# A-GSM.net
KiCad netlist of a schematic drawn in Altium Designer
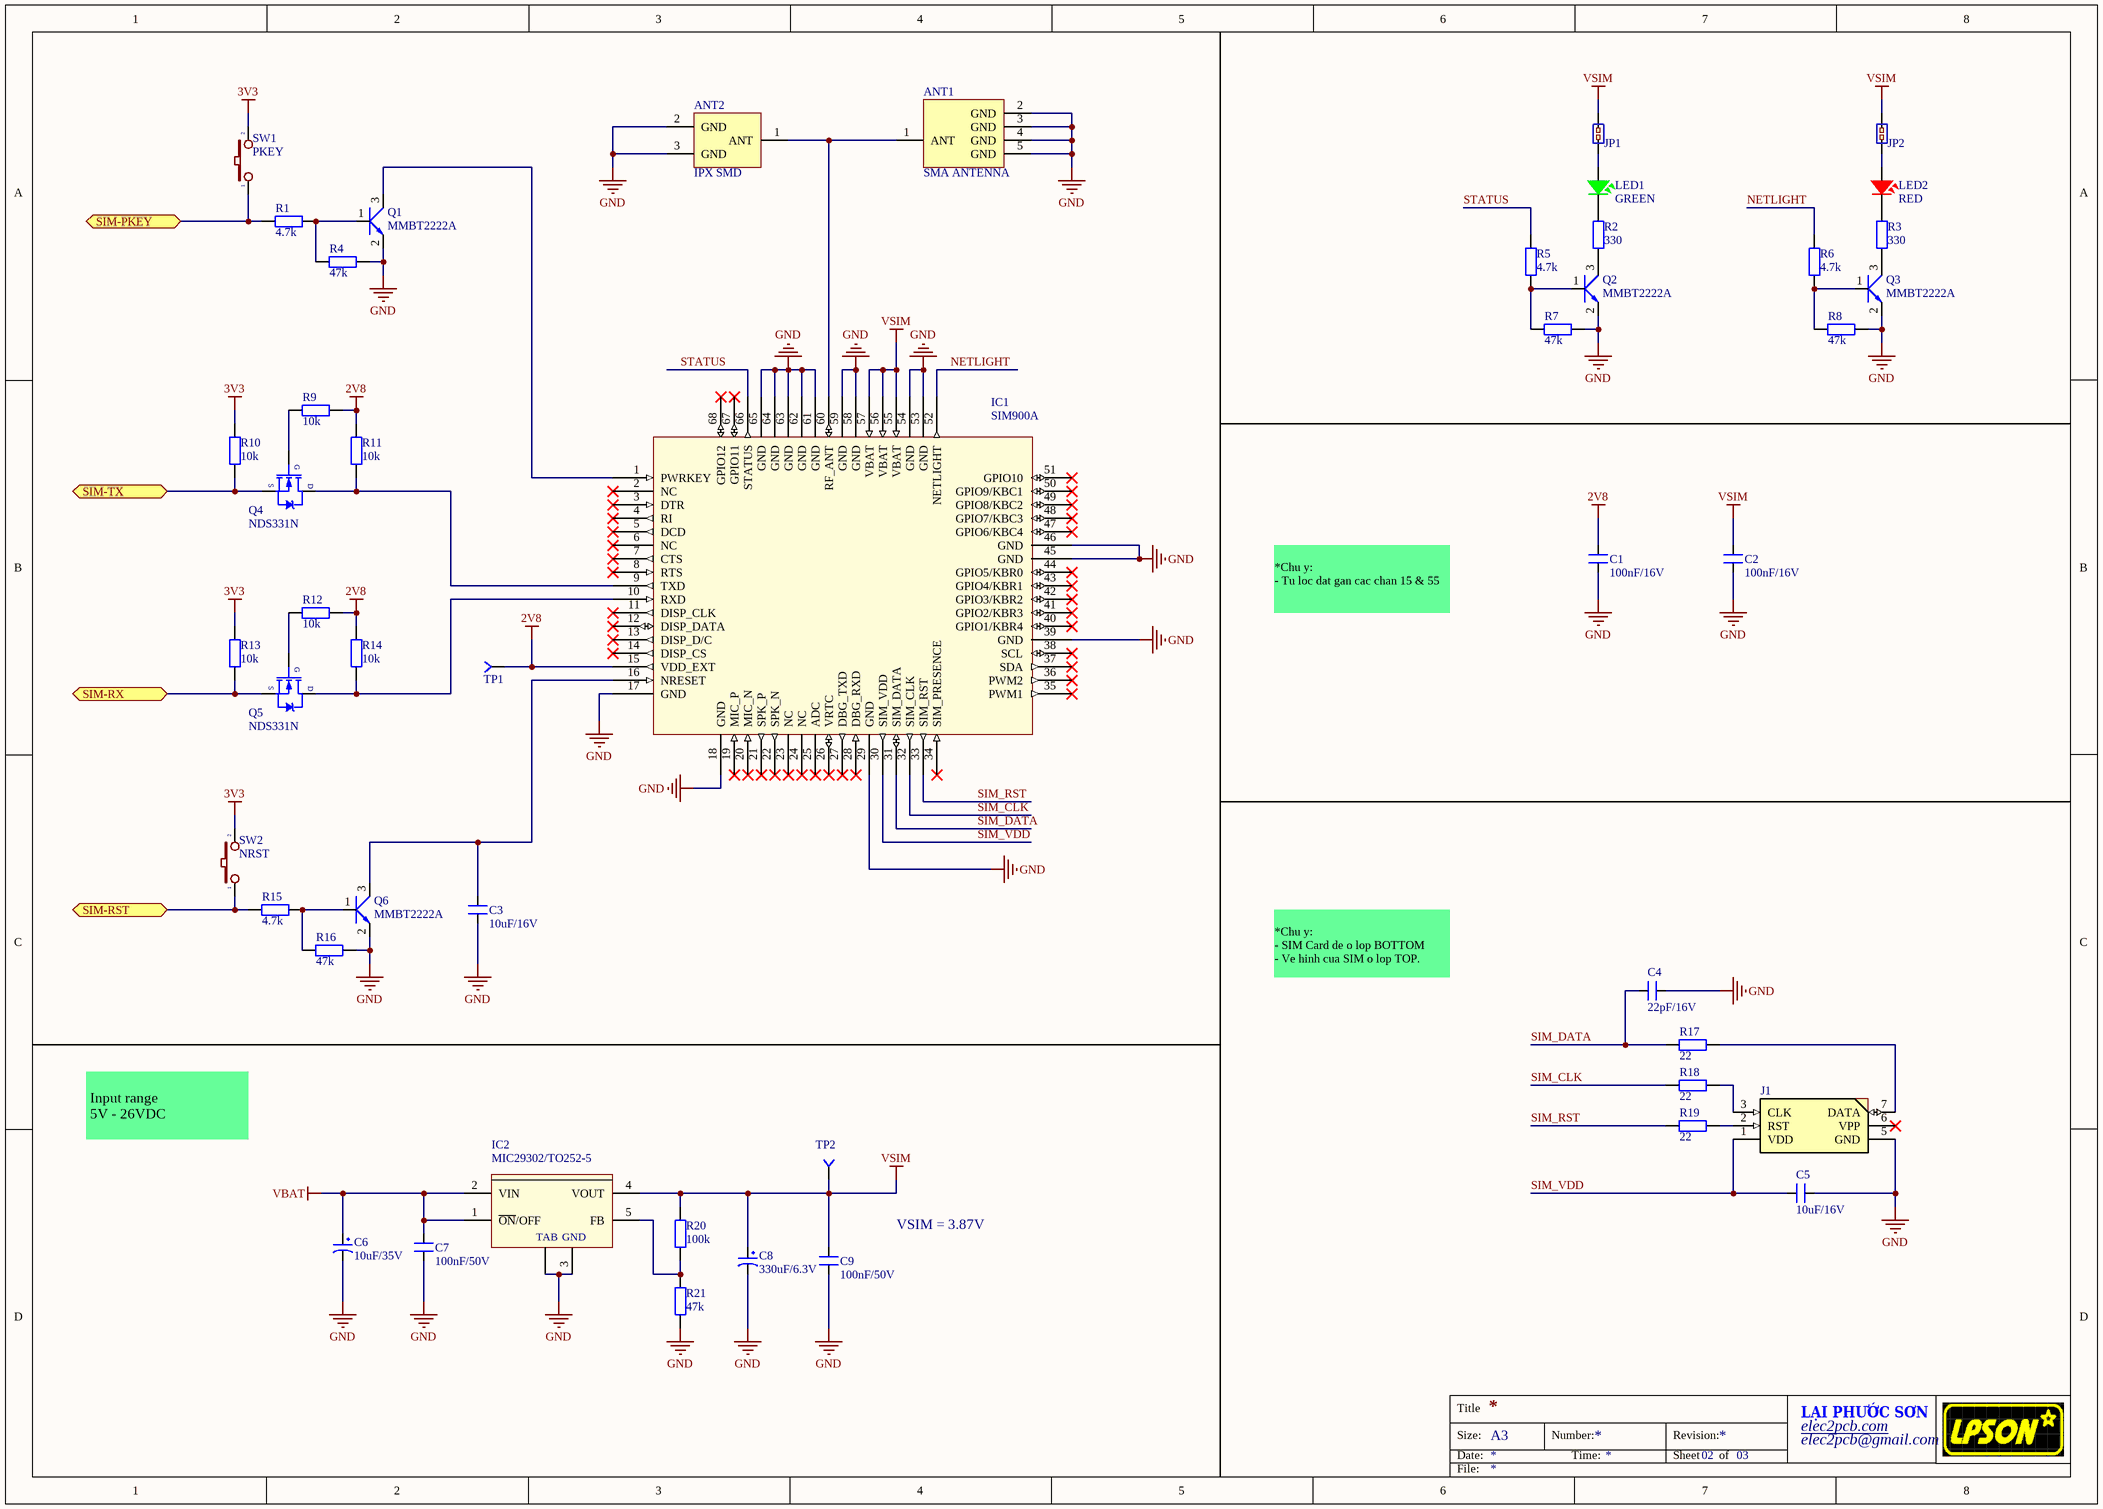
[diagram p0: A-GSM.SchDoc]

(export (version "E")
  (design (tool "Eeschema 10.0.6"))
  (components
    (comp (ref "ANT1")
      (value "SMA ANTENNA")
      (footprint "ANT-SMA-ST-F")
      (description "SMA Right-Angle PCB Female Antenna")
      (fields (field (name "Comment") "ANTEN-SMA"))
      (libsource (lib "Tran Tuan") (part "ANTEN-SMA"))
    )
    (comp (ref "ANT2")
      (value "IPX SMD")
      (footprint "ANT-IPX-SMD")
      (description "IPX, SMD, ANTENNA")
      (fields (field (name "Comment") "ANTEN-IPX"))
      (libsource (lib "Tran Tuan") (part "ANTEN-IPX"))
    )
    (comp (ref "C1")
      (value "100nF/16V")
      (footprint "C0805-2012")
      (description "CAP CER 0.1UF 16V X7R 0805")
      (fields
        (field (name "MANUFACTURER") "Kemet")
        (field (name "MANUFACTURER PART NUMBER") "C0805C104K4RACTU")
      )
      (libsource (lib "Tran Tuan") (part "CAP-CER/100nF/16V/X7R/0805"))
    )
    (comp (ref "C2")
      (value "100nF/16V")
      (footprint "C0805-2012")
      (description "CAP CER 0.1UF 16V X7R 0805")
      (fields
        (field (name "MANUFACTURER") "Kemet")
        (field (name "MANUFACTURER PART NUMBER") "C0805C104K4RACTU")
      )
      (libsource (lib "Tran Tuan") (part "CAP-CER/100nF/16V/X7R/0805"))
    )
    (comp (ref "C3")
      (value "10uF/16V")
      (footprint "C0805-2012")
      (description "CAP CER 10UF 16V X5R 0805")
      (fields
        (field (name "MANUFACTURER") "Murata Electronics North America")
        (field (name "MANUFACTURER PART NUMBER") "GRM21BR61C106KE15L")
      )
      (libsource (lib "Tran Tuan") (part "CAP-CER/10UF/16V/X5R/0805"))
    )
    (comp (ref "C4")
      (value "22pF/16V")
      (footprint "C0603-1608")
      (description "CAP CER 22PF 16V NP0 0603")
      (fields
        (field (name "MANUFACTURER") "Kemet")
        (field (name "MANUFACTURER PART NUMBER") "C0603C220K4GACTU")
      )
      (libsource (lib "Tran Tuan") (part "CAP-CER/22pF/16V/NP0/0603"))
    )
    (comp (ref "C5")
      (value "10uF/16V")
      (footprint "C0805-2012")
      (description "CAP CER 10UF 16V X5R 0805")
      (fields
        (field (name "MANUFACTURER") "Murata Electronics North America")
        (field (name "MANUFACTURER PART NUMBER") "GRM21BR61C106KE15L")
      )
      (libsource (lib "Tran Tuan") (part "CAP-CER/10UF/16V/X5R/0805"))
    )
    (comp (ref "C6")
      (value "10uF/35V")
      (footprint "CAP_TANTA_10UF_35V")
      (description "CAP TANT 10UF 35V 10% 2413")
      (fields
        (field (name "MANUFACTURER") "Kemet")
        (field (name "MANUFACTURER PART NUMBER") "T491C106K035AT")
      )
      (libsource (lib "Tran Tuan") (part "CAP-TANT/10uF/35V/2413"))
    )
    (comp (ref "C7")
      (value "100nF/50V")
      (footprint "C0805-2012")
      (description "CAP CER 0.1UF 50V X7R 0805")
      (fields
        (field (name "MANUFACTURER") "AVX Corporation")
        (field (name "MANUFACTURER PART NUMBER") "08055C104KAT2A")
      )
      (libsource (lib "Tran Tuan") (part "CAP-CER/100nF/50V/X7R/0805"))
    )
    (comp (ref "C8")
      (value "330uF/6.3V")
      (footprint "CAP_TANTA-3528")
      (description "CAP TAN 330UF 20% 6V 3528-21")
      (fields
        (field (name "MANUFACTURER") "Kemet")
        (field (name "MANUFACTURER PART NUMBER") "T490B337M006ATE800")
      )
      (libsource (lib "Tran Tuan") (part "CAP-TANT/330uF/6.3V/3528"))
    )
    (comp (ref "C9")
      (value "100nF/50V")
      (footprint "C0805-2012")
      (description "CAP CER 0.1UF 50V X7R 0805")
      (fields
        (field (name "MANUFACTURER") "AVX Corporation")
        (field (name "MANUFACTURER PART NUMBER") "08055C104KAT2A")
      )
      (libsource (lib "Tran Tuan") (part "CAP-CER/100nF/50V/X7R/0805"))
    )
    (comp (ref "IC1")
      (value "SIM900A/SIMCOM")
      (footprint "SIM900A")
      (description "SIM900A, Dual-band GSM/GPRS 900/1800MHz Module")
      (fields (field (name "MANUFACTURER") "SIMCOM") (field (name "MANUFACTURER PART NUMBER") "SIM900A"))
      (libsource (lib "Tran Tuan") (part "SIM900A/SIMCOM"))
    )
    (comp (ref "IC2")
      (value "MIC29302/TO252-5")
      (footprint "MIC29302A")
      (description "IC REG LDO ADJ 3A TO252-5")
      (fields
        (field (name "MANUFACTURER") "Microchip Technology")
        (field (name "MANUFACTURER PART NUMBER") "MIC29302AWD-TR")
      )
      (libsource (lib "Tran Tuan") (part "MIC29302/TO252-5"))
    )
    (comp (ref "J1")
      (value "SIM-FMS006-2620-0")
      (footprint "SIM-FMS006-2620-0")
      (description "SIM Card Conn 6-Pin Top, Mount, Push-Push")
      (libsource (lib "Tran Tuan") (part "SIM-FMS006-2620-0"))
    )
    (comp (ref "JP1")
      (value "JP2-ShortingJumper")
      (footprint "Header_2")
      (description "2.54mm 2-Pin Shorting Jumper")
      (libsource (lib "Tran Tuan") (part "JP2-ShortingJumper"))
    )
    (comp (ref "JP2")
      (value "JP2-ShortingJumper")
      (footprint "Header_2")
      (description "2.54mm 2-Pin Shorting Jumper")
      (libsource (lib "Tran Tuan") (part "JP2-ShortingJumper"))
    )
    (comp (ref "LED1")
      (value "GREEN")
      (footprint "Led 0805G")
      (description "LED GREEN CLEAR 0805 SMD")
      (fields
        (field (name "MANUFACTURER") "Lite-On Inc.")
        (field (name "MANUFACTURER PART NUMBER") "LTST-C171GKT")
      )
      (libsource (lib "Tran Tuan") (part "LED-GREEN/CLEAR/0805"))
    )
    (comp (ref "LED2")
      (value "RED")
      (footprint "Led 0805R")
      (description "LED RED CLEAR 0805 SMD")
      (fields
        (field (name "MANUFACTURER") "Lite-On Inc.")
        (field (name "MANUFACTURER PART NUMBER") "LTST-C171KRKT")
      )
      (libsource (lib "Tran Tuan") (part "LED-RED/CLEAR/0805"))
    )
    (comp (ref "Q1")
      (value "MMBT2222A")
      (footprint "MMBT2222A")
      (description "TRANS NPN 40V 0.6A SOT23")
      (fields
        (field (name "MANUFACTURER") "ON Semiconductor")
        (field (name "MANUFACTURER PART NUMBER") "MMBT2222ALT1G")
      )
      (libsource (lib "Tran Tuan") (part "BJT-MMBT2222A/SOT23"))
    )
    (comp (ref "Q2")
      (value "MMBT2222A")
      (footprint "MMBT2222A")
      (description "TRANS NPN 40V 0.6A SOT23")
      (fields
        (field (name "MANUFACTURER") "ON Semiconductor")
        (field (name "MANUFACTURER PART NUMBER") "MMBT2222ALT1G")
      )
      (libsource (lib "Tran Tuan") (part "BJT-MMBT2222A/SOT23"))
    )
    (comp (ref "Q3")
      (value "MMBT2222A")
      (footprint "MMBT2222A")
      (description "TRANS NPN 40V 0.6A SOT23")
      (fields
        (field (name "MANUFACTURER") "ON Semiconductor")
        (field (name "MANUFACTURER PART NUMBER") "MMBT2222ALT1G")
      )
      (libsource (lib "Tran Tuan") (part "BJT-MMBT2222A/SOT23"))
    )
    (comp (ref "Q4")
      (value "NDS331N")
      (footprint "NDS331N")
      (description "MOSFET N-CH 20V 1.3A SSOT3")
      (fields (field (name "MANUFACTURER") "Fairchild Semiconductor"))
      (libsource (lib "Tran Tuan") (part "MOSFET-NDS331N/SSOT3"))
    )
    (comp (ref "Q5")
      (value "NDS331N")
      (footprint "NDS331N")
      (description "MOSFET N-CH 20V 1.3A SSOT3")
      (fields (field (name "MANUFACTURER") "Fairchild Semiconductor"))
      (libsource (lib "Tran Tuan") (part "MOSFET-NDS331N/SSOT3"))
    )
    (comp (ref "Q6")
      (value "MMBT2222A")
      (footprint "MMBT2222A")
      (description "TRANS NPN 40V 0.6A SOT23")
      (fields
        (field (name "MANUFACTURER") "ON Semiconductor")
        (field (name "MANUFACTURER PART NUMBER") "MMBT2222ALT1G")
      )
      (libsource (lib "Tran Tuan") (part "BJT-MMBT2222A/SOT23"))
    )
    (comp (ref "R1")
      (value "~")
      (footprint "RESC2012(0805)")
      (description "RES SMD 4.7K OHM 5% 1/8W 0805")
      (fields
        (field (name "MANUFACTURER") "Yageo")
        (field (name "MANUFACTURER PART NUMBER") "RC0805JR-074K7L")
        (field (name "RESISTANCE (OHMS)") "4.7k")
      )
      (libsource (lib "") (part "RES-0805/±5%_3"))
    )
    (comp (ref "R2")
      (value "~")
      (footprint "RESC2012(0805)")
      (description "RES SMD 330 OHM 5% 1/8W 0805")
      (fields
        (field (name "MANUFACTURER") "Yageo")
        (field (name "MANUFACTURER PART NUMBER") "RC0805JR-07330RL")
        (field (name "RESISTANCE (OHMS)") "330")
      )
      (libsource (lib "") (part "RES-0805/±5%_2"))
    )
    (comp (ref "R3")
      (value "~")
      (footprint "RESC2012(0805)")
      (description "RES SMD 330 OHM 5% 1/8W 0805")
      (fields
        (field (name "MANUFACTURER") "Yageo")
        (field (name "MANUFACTURER PART NUMBER") "RC0805JR-07330RL")
        (field (name "RESISTANCE (OHMS)") "330")
      )
      (libsource (lib "") (part "RES-0805/±5%_2"))
    )
    (comp (ref "R4")
      (value "~")
      (footprint "RESC2012(0805)")
      (description "RES SMD 47K OHM 5% 1/8W 0805")
      (fields
        (field (name "MANUFACTURER") "Yageo")
        (field (name "MANUFACTURER PART NUMBER") "RC0805JR-0747KL")
        (field (name "RESISTANCE (OHMS)") "47k")
      )
      (libsource (lib "") (part "RES-0805/±5%_3"))
    )
    (comp (ref "R5")
      (value "~")
      (footprint "RESC2012(0805)")
      (description "RES SMD 4.7K OHM 5% 1/8W 0805")
      (fields
        (field (name "MANUFACTURER") "Yageo")
        (field (name "MANUFACTURER PART NUMBER") "RC0805JR-074K7L")
        (field (name "RESISTANCE (OHMS)") "4.7k")
      )
      (libsource (lib "") (part "RES-0805/±5%_2"))
    )
    (comp (ref "R6")
      (value "~")
      (footprint "RESC2012(0805)")
      (description "RES SMD 4.7K OHM 5% 1/8W 0805")
      (fields
        (field (name "MANUFACTURER") "Yageo")
        (field (name "MANUFACTURER PART NUMBER") "RC0805JR-074K7L")
        (field (name "RESISTANCE (OHMS)") "4.7k")
      )
      (libsource (lib "") (part "RES-0805/±5%_2"))
    )
    (comp (ref "R7")
      (value "~")
      (footprint "RESC2012(0805)")
      (description "RES SMD 47K OHM 5% 1/8W 0805")
      (fields
        (field (name "MANUFACTURER") "Yageo")
        (field (name "MANUFACTURER PART NUMBER") "RC0805JR-0747KL")
        (field (name "RESISTANCE (OHMS)") "47k")
      )
      (libsource (lib "") (part "RES-0805/±5%_3"))
    )
    (comp (ref "R8")
      (value "~")
      (footprint "RESC2012(0805)")
      (description "RES SMD 47K OHM 5% 1/8W 0805")
      (fields
        (field (name "MANUFACTURER") "Yageo")
        (field (name "MANUFACTURER PART NUMBER") "RC0805JR-0747KL")
        (field (name "RESISTANCE (OHMS)") "47k")
      )
      (libsource (lib "") (part "RES-0805/±5%_3"))
    )
    (comp (ref "R9")
      (value "~")
      (footprint "RESC2012(0805)")
      (description "RES SMD 10K OHM 5% 1/8W 0805")
      (fields
        (field (name "MANUFACTURER") "Yageo")
        (field (name "MANUFACTURER PART NUMBER") "RC0805JR-0710KL")
        (field (name "RESISTANCE (OHMS)") "10k")
      )
      (libsource (lib "") (part "RES-0805/±5%_3"))
    )
    (comp (ref "R10")
      (value "~")
      (footprint "RESC2012(0805)")
      (description "RES SMD 10K OHM 5% 1/8W 0805")
      (fields
        (field (name "MANUFACTURER") "Yageo")
        (field (name "MANUFACTURER PART NUMBER") "RC0805JR-0710KL")
        (field (name "RESISTANCE (OHMS)") "10k")
      )
      (libsource (lib "Tran Tuan") (part "RES-0805/±5%"))
    )
    (comp (ref "R11")
      (value "~")
      (footprint "RESC2012(0805)")
      (description "RES SMD 10K OHM 5% 1/8W 0805")
      (fields
        (field (name "MANUFACTURER") "Yageo")
        (field (name "MANUFACTURER PART NUMBER") "RC0805JR-0710KL")
        (field (name "RESISTANCE (OHMS)") "10k")
      )
      (libsource (lib "Tran Tuan") (part "RES-0805/±5%"))
    )
    (comp (ref "R12")
      (value "~")
      (footprint "RESC2012(0805)")
      (description "RES SMD 10K OHM 5% 1/8W 0805")
      (fields
        (field (name "MANUFACTURER") "Yageo")
        (field (name "MANUFACTURER PART NUMBER") "RC0805JR-0710KL")
        (field (name "RESISTANCE (OHMS)") "10k")
      )
      (libsource (lib "") (part "RES-0805/±5%_3"))
    )
    (comp (ref "R13")
      (value "~")
      (footprint "RESC2012(0805)")
      (description "RES SMD 10K OHM 5% 1/8W 0805")
      (fields
        (field (name "MANUFACTURER") "Yageo")
        (field (name "MANUFACTURER PART NUMBER") "RC0805JR-0710KL")
        (field (name "RESISTANCE (OHMS)") "10k")
      )
      (libsource (lib "Tran Tuan") (part "RES-0805/±5%"))
    )
    (comp (ref "R14")
      (value "~")
      (footprint "RESC2012(0805)")
      (description "RES SMD 10K OHM 5% 1/8W 0805")
      (fields
        (field (name "MANUFACTURER") "Yageo")
        (field (name "MANUFACTURER PART NUMBER") "RC0805JR-0710KL")
        (field (name "RESISTANCE (OHMS)") "10k")
      )
      (libsource (lib "Tran Tuan") (part "RES-0805/±5%"))
    )
    (comp (ref "R15")
      (value "~")
      (footprint "RESC2012(0805)")
      (description "RES SMD 4.7K OHM 5% 1/8W 0805")
      (fields
        (field (name "MANUFACTURER") "Yageo")
        (field (name "MANUFACTURER PART NUMBER") "RC0805JR-074K7L")
        (field (name "RESISTANCE (OHMS)") "4.7k")
      )
      (libsource (lib "") (part "RES-0805/±5%_3"))
    )
    (comp (ref "R16")
      (value "~")
      (footprint "RESC2012(0805)")
      (description "RES SMD 47K OHM 5% 1/8W 0805")
      (fields
        (field (name "MANUFACTURER") "Yageo")
        (field (name "MANUFACTURER PART NUMBER") "RC0805JR-0747KL")
        (field (name "RESISTANCE (OHMS)") "47k")
      )
      (libsource (lib "") (part "RES-0805/±5%_3"))
    )
    (comp (ref "R17")
      (value "~")
      (footprint "RESC2012(0805)")
      (description "RES SMD 22 OHM 5% 1/8W 0805")
      (fields
        (field (name "MANUFACTURER") "Yageo")
        (field (name "MANUFACTURER PART NUMBER") "RC0805JR-0722RL")
        (field (name "RESISTANCE (OHMS)") "22")
      )
      (libsource (lib "") (part "RES-0805/±5%_1"))
    )
    (comp (ref "R18")
      (value "~")
      (footprint "RESC2012(0805)")
      (description "RES SMD 22 OHM 5% 1/8W 0805")
      (fields
        (field (name "MANUFACTURER") "Yageo")
        (field (name "MANUFACTURER PART NUMBER") "RC0805JR-0722RL")
        (field (name "RESISTANCE (OHMS)") "22")
      )
      (libsource (lib "") (part "RES-0805/±5%_1"))
    )
    (comp (ref "R19")
      (value "~")
      (footprint "RESC2012(0805)")
      (description "RES SMD 22 OHM 5% 1/8W 0805")
      (fields
        (field (name "MANUFACTURER") "Yageo")
        (field (name "MANUFACTURER PART NUMBER") "RC0805JR-0722RL")
        (field (name "RESISTANCE (OHMS)") "22")
      )
      (libsource (lib "") (part "RES-0805/±5%_1"))
    )
    (comp (ref "R20")
      (value "~")
      (footprint "RESC2012(0805)")
      (description "RES SMD 100K OHM 5% 1/8W 0805")
      (fields
        (field (name "MANUFACTURER") "Yageo")
        (field (name "MANUFACTURER PART NUMBER") "RC0805JR-07100KL")
        (field (name "RESISTANCE (OHMS)") "100k")
      )
      (libsource (lib "Tran Tuan") (part "RES-0805/±5%"))
    )
    (comp (ref "R21")
      (value "~")
      (footprint "RESC2012(0805)")
      (description "RES SMD 47K OHM 5% 1/8W 0805")
      (fields
        (field (name "MANUFACTURER") "Yageo")
        (field (name "MANUFACTURER PART NUMBER") "RC0805JR-0747KL")
        (field (name "RESISTANCE (OHMS)") "47k")
      )
      (libsource (lib "") (part "RES-0805/±5%_2"))
    )
    (comp (ref "SW1")
      (value "PKEY")
      (footprint "BTN-EVQ-11A04M")
      (description "SWITCH TACTILE SPST-NO 0.02A 15V")
      (fields
        (field (name "MANUFACTURER") "Panasonic Electronic Components")
        (field (name "MANUFACTURER PART NUMBER") "EVQ-11A04M")
      )
      (libsource (lib "Tran Tuan") (part "SW2-PUSH/SPST/NO"))
    )
    (comp (ref "SW2")
      (value "NRST")
      (footprint "BTN-EVQ-11A04M")
      (description "SWITCH TACTILE SPST-NO 0.02A 15V")
      (fields
        (field (name "MANUFACTURER") "Panasonic Electronic Components")
        (field (name "MANUFACTURER PART NUMBER") "EVQ-11A04M")
      )
      (libsource (lib "Tran Tuan") (part "SW2-PUSH/SPST/NO"))
    )
    (comp (ref "TP1")
      (value "Test Point")
      (footprint "Test_point_VIA06")
      (description "Test Point, Pad, Hole")
      (libsource (lib "Tran Tuan") (part "Connector-TP"))
    )
    (comp (ref "TP2")
      (value "Test Point")
      (footprint "Test_point_VIA06")
      (description "Test Point, Pad, Hole")
      (libsource (lib "Tran Tuan") (part "Connector-TP"))
    )
  )
  (nets
    (net (code "1") (name "/NETLIGHT") (class "Default")
      (node (ref "IC1") (pin "52") (pinfunction "NETLIGHT_52") (pintype "output"))
      (node (ref "R6") (pin "2") (pinfunction "2_2") (pintype "passive"))
    )
    (net (code "2") (name "/SIM-PKEY") (class "Default")
      (node (ref "R1") (pin "1") (pinfunction "1_1") (pintype "passive"))
      (node (ref "SW1") (pin "1") (pinfunction "1_1") (pintype "passive"))
    )
    (net (code "3") (name "/SIM-RST") (class "Default")
      (node (ref "R15") (pin "1") (pinfunction "1_1") (pintype "passive"))
      (node (ref "SW2") (pin "1") (pinfunction "1_1") (pintype "passive"))
    )
    (net (code "4") (name "/SIM-RX") (class "Default")
      (node (ref "Q5") (pin "2") (pinfunction "S_2") (pintype "passive"))
      (node (ref "R13") (pin "2") (pinfunction "2_2") (pintype "passive"))
    )
    (net (code "5") (name "/SIM-TX") (class "Default")
      (node (ref "Q4") (pin "2") (pinfunction "S_2") (pintype "passive"))
      (node (ref "R10") (pin "2") (pinfunction "2_2") (pintype "passive"))
    )
    (net (code "6") (name "/SIM_CLK") (class "Default")
      (node (ref "IC1") (pin "32") (pinfunction "SIM_CLK_32") (pintype "output"))
      (node (ref "R18") (pin "2") (pinfunction "2_2") (pintype "passive"))
    )
    (net (code "7") (name "/SIM_DATA") (class "Default")
      (node (ref "C4") (pin "1") (pinfunction "1_1") (pintype "passive"))
      (node (ref "IC1") (pin "31") (pinfunction "SIM_DATA_31") (pintype "bidirectional"))
      (node (ref "R17") (pin "2") (pinfunction "2_2") (pintype "passive"))
    )
    (net (code "8") (name "/SIM_RST") (class "Default")
      (node (ref "IC1") (pin "33") (pinfunction "SIM_RST_33") (pintype "output"))
      (node (ref "R19") (pin "2") (pinfunction "2_2") (pintype "passive"))
    )
    (net (code "9") (name "/SIM_VDD") (class "Default")
      (node (ref "C5") (pin "1") (pinfunction "1_1") (pintype "passive"))
      (node (ref "IC1") (pin "30") (pinfunction "SIM_VDD_30") (pintype "output"))
      (node (ref "J1") (pin "1") (pinfunction "VDD_1") (pintype "passive"))
    )
    (net (code "10") (name "/STATUS") (class "Default")
      (node (ref "IC1") (pin "66") (pinfunction "STATUS_66") (pintype "output"))
      (node (ref "R5") (pin "2") (pinfunction "2_2") (pintype "passive"))
    )
    (net (code "11") (name "2V8") (class "Default")
      (node (ref "C1") (pin "1") (pinfunction "1_1") (pintype "passive"))
      (node (ref "IC1") (pin "15") (pinfunction "VDD_EXT_15") (pintype "output"))
      (node (ref "R11") (pin "1") (pinfunction "1_1") (pintype "passive"))
      (node (ref "R12") (pin "2") (pinfunction "2_2") (pintype "passive"))
      (node (ref "R14") (pin "1") (pinfunction "1_1") (pintype "passive"))
      (node (ref "R9") (pin "2") (pinfunction "2_2") (pintype "passive"))
      (node (ref "TP1") (pin "1") (pinfunction "1_1") (pintype "passive"))
    )
    (net (code "12") (name "3V3") (class "Default")
      (node (ref "R10") (pin "1") (pinfunction "1_1") (pintype "passive"))
      (node (ref "R13") (pin "1") (pinfunction "1_1") (pintype "passive"))
      (node (ref "SW1") (pin "2") (pinfunction "2_2") (pintype "passive"))
      (node (ref "SW2") (pin "2") (pinfunction "2_2") (pintype "passive"))
    )
    (net (code "13") (name "GND") (class "Default")
      (node (ref "ANT1") (pin "2") (pinfunction "GND_2") (pintype "power_in"))
      (node (ref "ANT1") (pin "3") (pinfunction "GND_3") (pintype "power_in"))
      (node (ref "ANT1") (pin "4") (pinfunction "GND_4") (pintype "power_in"))
      (node (ref "ANT1") (pin "5") (pinfunction "GND_5") (pintype "power_in"))
      (node (ref "ANT2") (pin "2") (pinfunction "GND_2") (pintype "power_in"))
      (node (ref "ANT2") (pin "3") (pinfunction "GND_3") (pintype "power_in"))
      (node (ref "C1") (pin "2") (pinfunction "2_2") (pintype "passive"))
      (node (ref "C2") (pin "2") (pinfunction "2_2") (pintype "passive"))
      (node (ref "C3") (pin "2") (pinfunction "2_2") (pintype "passive"))
      (node (ref "C4") (pin "2") (pinfunction "2_2") (pintype "passive"))
      (node (ref "C5") (pin "2") (pinfunction "2_2") (pintype "passive"))
      (node (ref "C6") (pin "2") (pinfunction "2_2") (pintype "passive"))
      (node (ref "C7") (pin "2") (pinfunction "2_2") (pintype "passive"))
      (node (ref "C8") (pin "2") (pinfunction "2_2") (pintype "passive"))
      (node (ref "C9") (pin "2") (pinfunction "2_2") (pintype "passive"))
      (node (ref "IC1") (pin "17") (pinfunction "GND_17") (pintype "power_in"))
      (node (ref "IC1") (pin "18") (pinfunction "GND_18") (pintype "power_in"))
      (node (ref "IC1") (pin "29") (pinfunction "GND_29") (pintype "power_in"))
      (node (ref "IC1") (pin "39") (pinfunction "GND_39") (pintype "power_in"))
      (node (ref "IC1") (pin "45") (pinfunction "GND_45") (pintype "power_in"))
      (node (ref "IC1") (pin "46") (pinfunction "GND_46") (pintype "power_in"))
      (node (ref "IC1") (pin "53") (pinfunction "GND_53") (pintype "power_in"))
      (node (ref "IC1") (pin "54") (pinfunction "GND_54") (pintype "power_in"))
      (node (ref "IC1") (pin "58") (pinfunction "GND_58") (pintype "power_in"))
      (node (ref "IC1") (pin "59") (pinfunction "GND_59") (pintype "power_in"))
      (node (ref "IC1") (pin "61") (pinfunction "GND_61") (pintype "power_in"))
      (node (ref "IC1") (pin "62") (pinfunction "GND_62") (pintype "power_in"))
      (node (ref "IC1") (pin "63") (pinfunction "GND_63") (pintype "power_in"))
      (node (ref "IC1") (pin "64") (pinfunction "GND_64") (pintype "power_in"))
      (node (ref "IC1") (pin "65") (pinfunction "GND_65") (pintype "power_in"))
      (node (ref "IC2") (pin "3") (pinfunction "GND_3") (pintype "power_in"))
      (node (ref "IC2") (pin "6") (pinfunction "TAB_6") (pintype "power_in"))
      (node (ref "J1") (pin "5") (pinfunction "GND_5") (pintype "passive"))
      (node (ref "Q1") (pin "2") (pinfunction "E_2") (pintype "passive"))
      (node (ref "Q2") (pin "2") (pinfunction "E_2") (pintype "passive"))
      (node (ref "Q3") (pin "2") (pinfunction "E_2") (pintype "passive"))
      (node (ref "Q6") (pin "2") (pinfunction "E_2") (pintype "passive"))
      (node (ref "R16") (pin "2") (pinfunction "2_2") (pintype "passive"))
      (node (ref "R21") (pin "1") (pinfunction "1_1") (pintype "passive"))
      (node (ref "R4") (pin "2") (pinfunction "2_2") (pintype "passive"))
      (node (ref "R7") (pin "2") (pinfunction "2_2") (pintype "passive"))
      (node (ref "R8") (pin "2") (pinfunction "2_2") (pintype "passive"))
    )
    (net (code "14") (name "Net-(ANT1-ANT)") (class "Default")
      (node (ref "ANT1") (pin "1") (pinfunction "ANT_1") (pintype "passive"))
      (node (ref "ANT2") (pin "1") (pinfunction "ANT_1") (pintype "passive"))
      (node (ref "IC1") (pin "60") (pinfunction "RF_ANT_60") (pintype "bidirectional"))
    )
    (net (code "15") (name "Net-(IC1-NRESET)") (class "Default")
      (node (ref "C3") (pin "1") (pinfunction "1_1") (pintype "passive"))
      (node (ref "IC1") (pin "16") (pinfunction "NRESET_16") (pintype "input"))
      (node (ref "Q6") (pin "3") (pinfunction "C_3") (pintype "passive"))
    )
    (net (code "16") (name "Net-(IC1-PWRKEY)") (class "Default")
      (node (ref "IC1") (pin "1") (pinfunction "PWRKEY_1") (pintype "input"))
      (node (ref "Q1") (pin "3") (pinfunction "C_3") (pintype "passive"))
    )
    (net (code "17") (name "Net-(IC1-RXD)") (class "Default")
      (node (ref "IC1") (pin "10") (pinfunction "RXD_10") (pintype "input"))
      (node (ref "Q5") (pin "3") (pinfunction "D_3") (pintype "passive"))
      (node (ref "R14") (pin "2") (pinfunction "2_2") (pintype "passive"))
    )
    (net (code "18") (name "Net-(IC1-TXD)") (class "Default")
      (node (ref "IC1") (pin "9") (pinfunction "TXD_9") (pintype "output"))
      (node (ref "Q4") (pin "3") (pinfunction "D_3") (pintype "passive"))
      (node (ref "R11") (pin "2") (pinfunction "2_2") (pintype "passive"))
    )
    (net (code "19") (name "Net-(IC2-FB)") (class "Default")
      (node (ref "IC2") (pin "5") (pinfunction "FB_5") (pintype "power_in"))
      (node (ref "R20") (pin "2") (pinfunction "2_2") (pintype "passive"))
      (node (ref "R21") (pin "2") (pinfunction "2_2") (pintype "passive"))
    )
    (net (code "20") (name "Net-(J1-CLK)") (class "Default")
      (node (ref "J1") (pin "3") (pinfunction "CLK_3") (pintype "input"))
      (node (ref "R18") (pin "1") (pinfunction "1_1") (pintype "passive"))
    )
    (net (code "21") (name "Net-(J1-DATA)") (class "Default")
      (node (ref "J1") (pin "7") (pinfunction "DATA_7") (pintype "bidirectional"))
      (node (ref "R17") (pin "1") (pinfunction "1_1") (pintype "passive"))
    )
    (net (code "22") (name "Net-(J1-RST)") (class "Default")
      (node (ref "J1") (pin "2") (pinfunction "RST_2") (pintype "input"))
      (node (ref "R19") (pin "1") (pinfunction "1_1") (pintype "passive"))
    )
    (net (code "23") (name "Net-(LED1-A)") (class "Default")
      (node (ref "JP1") (pin "1") (pinfunction "1_1") (pintype "passive"))
      (node (ref "LED1") (pin "1") (pinfunction "A_1") (pintype "passive"))
    )
    (net (code "24") (name "Net-(LED1-K)") (class "Default")
      (node (ref "LED1") (pin "2") (pinfunction "K_2") (pintype "passive"))
      (node (ref "R2") (pin "2") (pinfunction "2_2") (pintype "passive"))
    )
    (net (code "25") (name "Net-(LED2-A)") (class "Default")
      (node (ref "JP2") (pin "1") (pinfunction "1_1") (pintype "passive"))
      (node (ref "LED2") (pin "1") (pinfunction "A_1") (pintype "passive"))
    )
    (net (code "26") (name "Net-(LED2-K)") (class "Default")
      (node (ref "LED2") (pin "2") (pinfunction "K_2") (pintype "passive"))
      (node (ref "R3") (pin "2") (pinfunction "2_2") (pintype "passive"))
    )
    (net (code "27") (name "Net-(Q1-B)") (class "Default")
      (node (ref "Q1") (pin "1") (pinfunction "B_1") (pintype "passive"))
      (node (ref "R1") (pin "2") (pinfunction "2_2") (pintype "passive"))
      (node (ref "R4") (pin "1") (pinfunction "1_1") (pintype "passive"))
    )
    (net (code "28") (name "Net-(Q2-B)") (class "Default")
      (node (ref "Q2") (pin "1") (pinfunction "B_1") (pintype "passive"))
      (node (ref "R5") (pin "1") (pinfunction "1_1") (pintype "passive"))
      (node (ref "R7") (pin "1") (pinfunction "1_1") (pintype "passive"))
    )
    (net (code "29") (name "Net-(Q2-C)") (class "Default")
      (node (ref "Q2") (pin "3") (pinfunction "C_3") (pintype "passive"))
      (node (ref "R2") (pin "1") (pinfunction "1_1") (pintype "passive"))
    )
    (net (code "30") (name "Net-(Q3-B)") (class "Default")
      (node (ref "Q3") (pin "1") (pinfunction "B_1") (pintype "passive"))
      (node (ref "R6") (pin "1") (pinfunction "1_1") (pintype "passive"))
      (node (ref "R8") (pin "1") (pinfunction "1_1") (pintype "passive"))
    )
    (net (code "31") (name "Net-(Q3-C)") (class "Default")
      (node (ref "Q3") (pin "3") (pinfunction "C_3") (pintype "passive"))
      (node (ref "R3") (pin "1") (pinfunction "1_1") (pintype "passive"))
    )
    (net (code "32") (name "Net-(Q4-G)") (class "Default")
      (node (ref "Q4") (pin "1") (pinfunction "G_1") (pintype "passive"))
      (node (ref "R9") (pin "1") (pinfunction "1_1") (pintype "passive"))
    )
    (net (code "33") (name "Net-(Q5-G)") (class "Default")
      (node (ref "Q5") (pin "1") (pinfunction "G_1") (pintype "passive"))
      (node (ref "R12") (pin "1") (pinfunction "1_1") (pintype "passive"))
    )
    (net (code "34") (name "Net-(Q6-B)") (class "Default")
      (node (ref "Q6") (pin "1") (pinfunction "B_1") (pintype "passive"))
      (node (ref "R15") (pin "2") (pinfunction "2_2") (pintype "passive"))
      (node (ref "R16") (pin "1") (pinfunction "1_1") (pintype "passive"))
    )
    (net (code "35") (name "VBAT") (class "Default")
      (node (ref "C6") (pin "1") (pinfunction "1_1") (pintype "passive"))
      (node (ref "C7") (pin "1") (pinfunction "1_1") (pintype "passive"))
      (node (ref "IC2") (pin "1") (pinfunction "~{ON}/OFF_1") (pintype "power_in"))
      (node (ref "IC2") (pin "2") (pinfunction "VIN_2") (pintype "power_in"))
    )
    (net (code "36") (name "VSIM") (class "Default")
      (node (ref "C2") (pin "1") (pinfunction "1_1") (pintype "passive"))
      (node (ref "C8") (pin "1") (pinfunction "1_1") (pintype "passive"))
      (node (ref "C9") (pin "1") (pinfunction "1_1") (pintype "passive"))
      (node (ref "IC1") (pin "55") (pinfunction "VBAT_55") (pintype "input"))
      (node (ref "IC1") (pin "56") (pinfunction "VBAT_56") (pintype "input"))
      (node (ref "IC1") (pin "57") (pinfunction "VBAT_57") (pintype "input"))
      (node (ref "IC2") (pin "4") (pinfunction "VOUT_4") (pintype "power_in"))
      (node (ref "JP1") (pin "2") (pinfunction "2_2") (pintype "passive"))
      (node (ref "JP2") (pin "2") (pinfunction "2_2") (pintype "passive"))
      (node (ref "R20") (pin "1") (pinfunction "1_1") (pintype "passive"))
      (node (ref "TP2") (pin "1") (pinfunction "1_1") (pintype "passive"))
    )
    (net (code "37") (name "unconnected-(IC1-ADC-Pad25)") (class "Default")
      (node (ref "IC1") (pin "25") (pinfunction "ADC_25") (pintype "passive+no_connect"))
    )
    (net (code "38") (name "unconnected-(IC1-CTS-Pad7)") (class "Default")
      (node (ref "IC1") (pin "7") (pinfunction "CTS_7") (pintype "output+no_connect"))
    )
    (net (code "39") (name "unconnected-(IC1-DBG_RXD-Pad28)") (class "Default")
      (node (ref "IC1") (pin "28") (pinfunction "DBG_RXD_28") (pintype "input+no_connect"))
    )
    (net (code "40") (name "unconnected-(IC1-DBG_TXD-Pad27)") (class "Default")
      (node (ref "IC1") (pin "27") (pinfunction "DBG_TXD_27") (pintype "output+no_connect"))
    )
    (net (code "41") (name "unconnected-(IC1-DCD-Pad5)") (class "Default")
      (node (ref "IC1") (pin "5") (pinfunction "DCD_5") (pintype "output+no_connect"))
    )
    (net (code "42") (name "unconnected-(IC1-DISP_CLK-Pad11)") (class "Default")
      (node (ref "IC1") (pin "11") (pinfunction "DISP_CLK_11") (pintype "output+no_connect"))
    )
    (net (code "43") (name "unconnected-(IC1-DISP_CS-Pad14)") (class "Default")
      (node (ref "IC1") (pin "14") (pinfunction "DISP_CS_14") (pintype "output+no_connect"))
    )
    (net (code "44") (name "unconnected-(IC1-DISP_DATA-Pad12)") (class "Default")
      (node (ref "IC1") (pin "12") (pinfunction "DISP_DATA_12") (pintype "bidirectional+no_connect"))
    )
    (net (code "45") (name "unconnected-(IC1-DISP_D{slash}C-Pad13)") (class "Default")
      (node (ref "IC1") (pin "13") (pinfunction "DISP_D/C_13") (pintype "output+no_connect"))
    )
    (net (code "46") (name "unconnected-(IC1-DTR-Pad3)") (class "Default")
      (node (ref "IC1") (pin "3") (pinfunction "DTR_3") (pintype "input+no_connect"))
    )
    (net (code "47") (name "unconnected-(IC1-GPIO1{slash}KBR4-Pad40)") (class "Default")
      (node (ref "IC1") (pin "40") (pinfunction "GPIO1/KBR4_40") (pintype "bidirectional+no_connect"))
    )
    (net (code "48") (name "unconnected-(IC1-GPIO2{slash}KBR3-Pad41)") (class "Default")
      (node (ref "IC1") (pin "41") (pinfunction "GPIO2/KBR3_41") (pintype "bidirectional+no_connect"))
    )
    (net (code "49") (name "unconnected-(IC1-GPIO3{slash}KBR2-Pad42)") (class "Default")
      (node (ref "IC1") (pin "42") (pinfunction "GPIO3/KBR2_42") (pintype "bidirectional+no_connect"))
    )
    (net (code "50") (name "unconnected-(IC1-GPIO4{slash}KBR1-Pad43)") (class "Default")
      (node (ref "IC1") (pin "43") (pinfunction "GPIO4/KBR1_43") (pintype "bidirectional+no_connect"))
    )
    (net (code "51") (name "unconnected-(IC1-GPIO5{slash}KBR0-Pad44)") (class "Default")
      (node (ref "IC1") (pin "44") (pinfunction "GPIO5/KBR0_44") (pintype "bidirectional+no_connect"))
    )
    (net (code "52") (name "unconnected-(IC1-GPIO6{slash}KBC4-Pad47)") (class "Default")
      (node (ref "IC1") (pin "47") (pinfunction "GPIO6/KBC4_47") (pintype "bidirectional+no_connect"))
    )
    (net (code "53") (name "unconnected-(IC1-GPIO7{slash}KBC3-Pad48)") (class "Default")
      (node (ref "IC1") (pin "48") (pinfunction "GPIO7/KBC3_48") (pintype "bidirectional+no_connect"))
    )
    (net (code "54") (name "unconnected-(IC1-GPIO8{slash}KBC2-Pad49)") (class "Default")
      (node (ref "IC1") (pin "49") (pinfunction "GPIO8/KBC2_49") (pintype "bidirectional+no_connect"))
    )
    (net (code "55") (name "unconnected-(IC1-GPIO9{slash}KBC1-Pad50)") (class "Default")
      (node (ref "IC1") (pin "50") (pinfunction "GPIO9/KBC1_50") (pintype "bidirectional+no_connect"))
    )
    (net (code "56") (name "unconnected-(IC1-GPIO10-Pad51)") (class "Default")
      (node (ref "IC1") (pin "51") (pinfunction "GPIO10_51") (pintype "bidirectional+no_connect"))
    )
    (net (code "57") (name "unconnected-(IC1-GPIO11-Pad67)") (class "Default")
      (node (ref "IC1") (pin "67") (pinfunction "GPIO11_67") (pintype "bidirectional+no_connect"))
    )
    (net (code "58") (name "unconnected-(IC1-GPIO12-Pad68)") (class "Default")
      (node (ref "IC1") (pin "68") (pinfunction "GPIO12_68") (pintype "bidirectional+no_connect"))
    )
    (net (code "59") (name "unconnected-(IC1-MIC_N-Pad20)") (class "Default")
      (node (ref "IC1") (pin "20") (pinfunction "MIC_N_20") (pintype "input+no_connect"))
    )
    (net (code "60") (name "unconnected-(IC1-MIC_P-Pad19)") (class "Default")
      (node (ref "IC1") (pin "19") (pinfunction "MIC_P_19") (pintype "input+no_connect"))
    )
    (net (code "61") (name "unconnected-(IC1-NC-Pad2)") (class "Default")
      (node (ref "IC1") (pin "2") (pinfunction "NC_2") (pintype "tri_state+no_connect"))
    )
    (net (code "62") (name "unconnected-(IC1-NC-Pad6)") (class "Default")
      (node (ref "IC1") (pin "6") (pinfunction "NC_6") (pintype "tri_state+no_connect"))
    )
    (net (code "63") (name "unconnected-(IC1-NC-Pad23)") (class "Default")
      (node (ref "IC1") (pin "23") (pinfunction "NC_23") (pintype "tri_state+no_connect"))
    )
    (net (code "64") (name "unconnected-(IC1-NC-Pad24)") (class "Default")
      (node (ref "IC1") (pin "24") (pinfunction "NC_24") (pintype "tri_state+no_connect"))
    )
    (net (code "65") (name "unconnected-(IC1-PWM1-Pad35)") (class "Default")
      (node (ref "IC1") (pin "35") (pinfunction "PWM1_35") (pintype "output+no_connect"))
    )
    (net (code "66") (name "unconnected-(IC1-PWM2-Pad36)") (class "Default")
      (node (ref "IC1") (pin "36") (pinfunction "PWM2_36") (pintype "output+no_connect"))
    )
    (net (code "67") (name "unconnected-(IC1-RI-Pad4)") (class "Default")
      (node (ref "IC1") (pin "4") (pinfunction "RI_4") (pintype "output+no_connect"))
    )
    (net (code "68") (name "unconnected-(IC1-RTS-Pad8)") (class "Default")
      (node (ref "IC1") (pin "8") (pinfunction "RTS_8") (pintype "input+no_connect"))
    )
    (net (code "69") (name "unconnected-(IC1-SCL-Pad38)") (class "Default")
      (node (ref "IC1") (pin "38") (pinfunction "SCL_38") (pintype "bidirectional+no_connect"))
    )
    (net (code "70") (name "unconnected-(IC1-SDA-Pad37)") (class "Default")
      (node (ref "IC1") (pin "37") (pinfunction "SDA_37") (pintype "output+no_connect"))
    )
    (net (code "71") (name "unconnected-(IC1-SIM_PRESENCE-Pad34)") (class "Default")
      (node (ref "IC1") (pin "34") (pinfunction "SIM_PRESENCE_34") (pintype "input+no_connect"))
    )
    (net (code "72") (name "unconnected-(IC1-SPK_N-Pad22)") (class "Default")
      (node (ref "IC1") (pin "22") (pinfunction "SPK_N_22") (pintype "output+no_connect"))
    )
    (net (code "73") (name "unconnected-(IC1-SPK_P-Pad21)") (class "Default")
      (node (ref "IC1") (pin "21") (pinfunction "SPK_P_21") (pintype "output+no_connect"))
    )
    (net (code "74") (name "unconnected-(IC1-VRTC-Pad26)") (class "Default")
      (node (ref "IC1") (pin "26") (pinfunction "VRTC_26") (pintype "bidirectional+no_connect"))
    )
    (net (code "75") (name "unconnected-(J1-VPP-Pad6)") (class "Default")
      (node (ref "J1") (pin "6") (pinfunction "VPP_6") (pintype "passive+no_connect"))
    )
  )
)
